# Relay_board.net
KiCad netlist of a schematic drawn in EAGLE
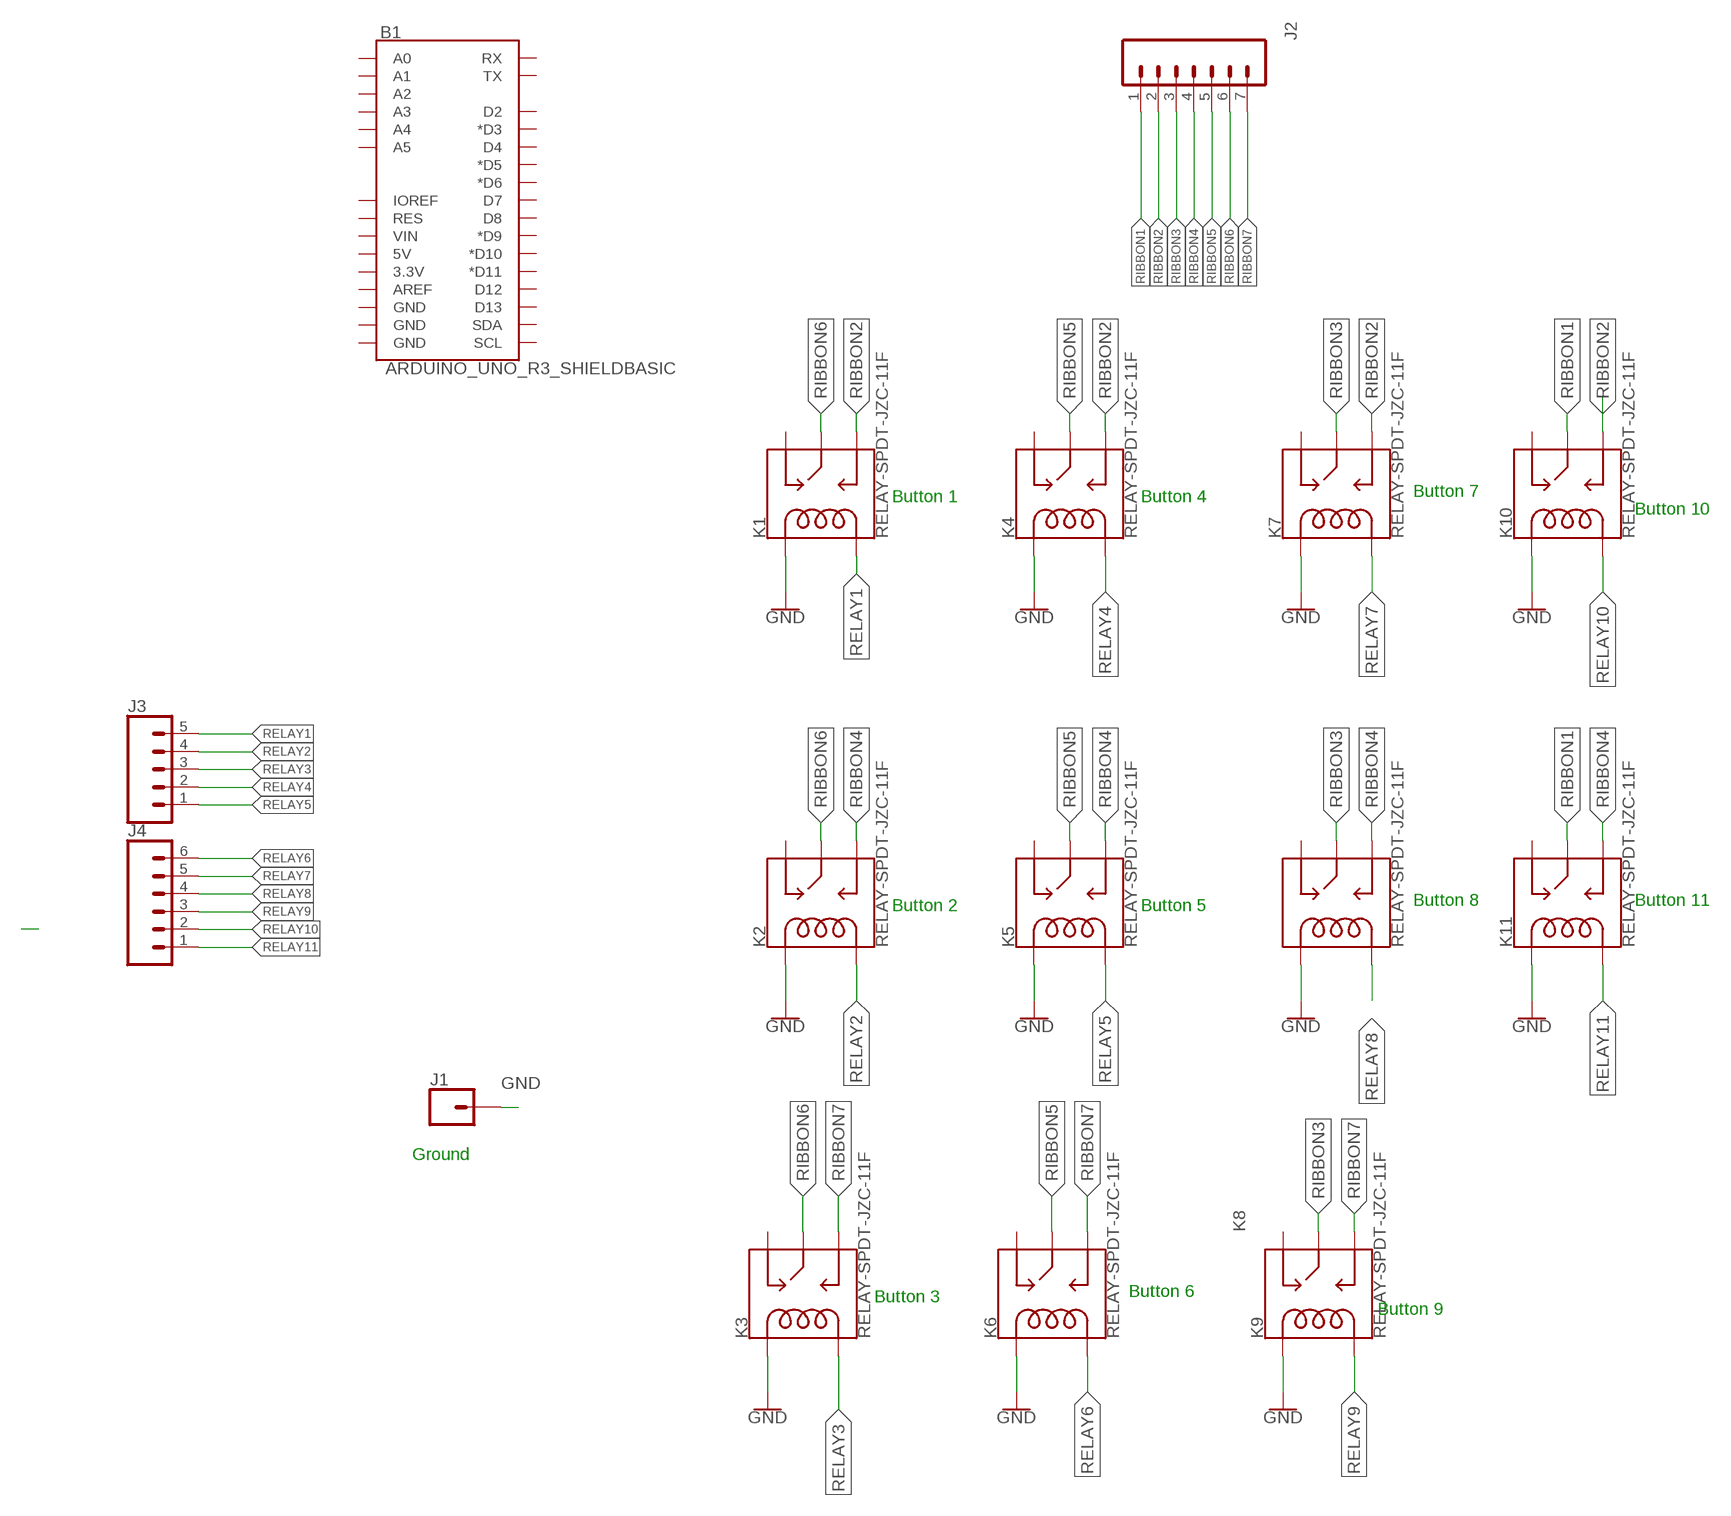
[diagram p0: schematic, sheet 1]

(export (version "E")
  (design (tool "Eeschema 10.0.6"))
  (components
    (comp (ref "B1")
      (value "ARDUINO_UNO_R3_SHIELDBASIC")
      (footprint "eagle-import:UNO_R3_SHIELD")
      (libsource (lib "eagle-import") (part "ARDUINO_UNO_R3_SHIELDBASIC"))
    )
    (comp (ref "J1")
      (value "CONN_01")
      (footprint "eagle-import:1X01")
      (libsource (lib "eagle-import") (part "CONN_01"))
    )
    (comp (ref "J2")
      (value "CONN_07")
      (footprint "eagle-import:1X07")
      (libsource (lib "eagle-import") (part "CONN_07"))
    )
    (comp (ref "J3")
      (value "CONN_05")
      (footprint "eagle-import:1X05")
      (libsource (lib "eagle-import") (part "CONN_05"))
    )
    (comp (ref "J4")
      (value "CONN_06SILK_FEMALE_PTH")
      (footprint "eagle-import:1X06")
      (libsource (lib "eagle-import") (part "CONN_06SILK_FEMALE_PTH"))
    )
    (comp (ref "K1")
      (value "RELAY-SPDT-JZC-11F")
      (footprint "eagle-import:RELAY-JZC")
      (libsource (lib "eagle-import") (part "RELAY-SPDT-JZC-11F"))
    )
    (comp (ref "K2")
      (value "RELAY-SPDT-JZC-11F")
      (footprint "eagle-import:RELAY-JZC")
      (libsource (lib "eagle-import") (part "RELAY-SPDT-JZC-11F"))
    )
    (comp (ref "K3")
      (value "RELAY-SPDT-JZC-11F")
      (footprint "eagle-import:RELAY-JZC")
      (libsource (lib "eagle-import") (part "RELAY-SPDT-JZC-11F"))
    )
    (comp (ref "K4")
      (value "RELAY-SPDT-JZC-11F")
      (footprint "eagle-import:RELAY-JZC")
      (libsource (lib "eagle-import") (part "RELAY-SPDT-JZC-11F"))
    )
    (comp (ref "K5")
      (value "RELAY-SPDT-JZC-11F")
      (footprint "eagle-import:RELAY-JZC")
      (libsource (lib "eagle-import") (part "RELAY-SPDT-JZC-11F"))
    )
    (comp (ref "K6")
      (value "RELAY-SPDT-JZC-11F")
      (footprint "eagle-import:RELAY-JZC")
      (libsource (lib "eagle-import") (part "RELAY-SPDT-JZC-11F"))
    )
    (comp (ref "K7")
      (value "RELAY-SPDT-JZC-11F")
      (footprint "eagle-import:RELAY-JZC")
      (libsource (lib "eagle-import") (part "RELAY-SPDT-JZC-11F"))
    )
    (comp (ref "K8")
      (value "RELAY-SPDT-JZC-11F")
      (footprint "eagle-import:RELAY-JZC")
      (libsource (lib "eagle-import") (part "RELAY-SPDT-JZC-11F"))
    )
    (comp (ref "K9")
      (value "RELAY-SPDT-JZC-11F")
      (footprint "eagle-import:RELAY-JZC")
      (libsource (lib "eagle-import") (part "RELAY-SPDT-JZC-11F"))
    )
    (comp (ref "K10")
      (value "RELAY-SPDT-JZC-11F")
      (footprint "eagle-import:RELAY-JZC")
      (libsource (lib "eagle-import") (part "RELAY-SPDT-JZC-11F"))
    )
    (comp (ref "K11")
      (value "RELAY-SPDT-JZC-11F")
      (footprint "eagle-import:RELAY-JZC")
      (libsource (lib "eagle-import") (part "RELAY-SPDT-JZC-11F"))
    )
  )
  (nets
    (net (code "1") (name "GND") (class "Default")
      (node (ref "J1") (pin "1") (pinfunction "1_1") (pintype "passive"))
      (node (ref "K1") (pin "5") (pinfunction "COIL1_5") (pintype "bidirectional"))
      (node (ref "K10") (pin "5") (pinfunction "COIL1_5") (pintype "bidirectional"))
      (node (ref "K11") (pin "5") (pinfunction "COIL1_5") (pintype "bidirectional"))
      (node (ref "K2") (pin "5") (pinfunction "COIL1_5") (pintype "bidirectional"))
      (node (ref "K3") (pin "5") (pinfunction "COIL1_5") (pintype "bidirectional"))
      (node (ref "K4") (pin "5") (pinfunction "COIL1_5") (pintype "bidirectional"))
      (node (ref "K5") (pin "5") (pinfunction "COIL1_5") (pintype "bidirectional"))
      (node (ref "K6") (pin "5") (pinfunction "COIL1_5") (pintype "bidirectional"))
      (node (ref "K7") (pin "5") (pinfunction "COIL1_5") (pintype "bidirectional"))
      (node (ref "K8") (pin "5") (pinfunction "COIL1_5") (pintype "bidirectional"))
      (node (ref "K9") (pin "5") (pinfunction "COIL1_5") (pintype "bidirectional"))
    )
    (net (code "2") (name "RELAY1") (class "Default")
      (node (ref "J3") (pin "5") (pinfunction "5_5") (pintype "passive"))
      (node (ref "K1") (pin "1") (pinfunction "COIL2_1") (pintype "bidirectional"))
    )
    (net (code "3") (name "RELAY2") (class "Default")
      (node (ref "J3") (pin "4") (pinfunction "4_4") (pintype "passive"))
      (node (ref "K2") (pin "1") (pinfunction "COIL2_1") (pintype "bidirectional"))
    )
    (net (code "4") (name "RELAY3") (class "Default")
      (node (ref "J3") (pin "3") (pinfunction "3_3") (pintype "passive"))
      (node (ref "K3") (pin "1") (pinfunction "COIL2_1") (pintype "bidirectional"))
    )
    (net (code "5") (name "RELAY4") (class "Default")
      (node (ref "J3") (pin "2") (pinfunction "2_2") (pintype "passive"))
      (node (ref "K4") (pin "1") (pinfunction "COIL2_1") (pintype "bidirectional"))
    )
    (net (code "6") (name "RELAY5") (class "Default")
      (node (ref "J3") (pin "1") (pinfunction "1_1") (pintype "passive"))
      (node (ref "K5") (pin "1") (pinfunction "COIL2_1") (pintype "bidirectional"))
    )
    (net (code "7") (name "RELAY6") (class "Default")
      (node (ref "J4") (pin "6") (pinfunction "6_6") (pintype "passive"))
      (node (ref "K6") (pin "1") (pinfunction "COIL2_1") (pintype "bidirectional"))
    )
    (net (code "8") (name "RELAY7") (class "Default")
      (node (ref "J4") (pin "5") (pinfunction "5_5") (pintype "passive"))
      (node (ref "K7") (pin "1") (pinfunction "COIL2_1") (pintype "bidirectional"))
    )
    (net (code "9") (name "RELAY8") (class "Default")
      (node (ref "J4") (pin "4") (pinfunction "4_4") (pintype "passive"))
      (node (ref "K8") (pin "1") (pinfunction "COIL2_1") (pintype "bidirectional"))
    )
    (net (code "10") (name "RELAY9") (class "Default")
      (node (ref "J4") (pin "3") (pinfunction "3_3") (pintype "passive"))
      (node (ref "K9") (pin "1") (pinfunction "COIL2_1") (pintype "bidirectional"))
    )
    (net (code "11") (name "RELAY10") (class "Default")
      (node (ref "J4") (pin "2") (pinfunction "2_2") (pintype "passive"))
      (node (ref "K10") (pin "1") (pinfunction "COIL2_1") (pintype "bidirectional"))
    )
    (net (code "12") (name "RELAY11") (class "Default")
      (node (ref "J4") (pin "1") (pinfunction "1_1") (pintype "passive"))
      (node (ref "K11") (pin "1") (pinfunction "COIL2_1") (pintype "bidirectional"))
    )
    (net (code "13") (name "RIBBON1") (class "Default")
      (node (ref "J2") (pin "1") (pinfunction "1_1") (pintype "passive"))
      (node (ref "K10") (pin "4") (pinfunction "MAIN_4") (pintype "bidirectional"))
      (node (ref "K11") (pin "4") (pinfunction "MAIN_4") (pintype "bidirectional"))
    )
    (net (code "14") (name "RIBBON2") (class "Default")
      (node (ref "J2") (pin "2") (pinfunction "2_2") (pintype "passive"))
      (node (ref "K1") (pin "3") (pinfunction "NO_3") (pintype "bidirectional"))
      (node (ref "K10") (pin "3") (pinfunction "NO_3") (pintype "bidirectional"))
      (node (ref "K4") (pin "3") (pinfunction "NO_3") (pintype "bidirectional"))
      (node (ref "K7") (pin "3") (pinfunction "NO_3") (pintype "bidirectional"))
    )
    (net (code "15") (name "RIBBON3") (class "Default")
      (node (ref "J2") (pin "3") (pinfunction "3_3") (pintype "passive"))
      (node (ref "K7") (pin "4") (pinfunction "MAIN_4") (pintype "bidirectional"))
      (node (ref "K8") (pin "4") (pinfunction "MAIN_4") (pintype "bidirectional"))
      (node (ref "K9") (pin "4") (pinfunction "MAIN_4") (pintype "bidirectional"))
    )
    (net (code "16") (name "RIBBON4") (class "Default")
      (node (ref "J2") (pin "4") (pinfunction "4_4") (pintype "passive"))
      (node (ref "K11") (pin "3") (pinfunction "NO_3") (pintype "bidirectional"))
      (node (ref "K2") (pin "3") (pinfunction "NO_3") (pintype "bidirectional"))
      (node (ref "K5") (pin "3") (pinfunction "NO_3") (pintype "bidirectional"))
      (node (ref "K8") (pin "3") (pinfunction "NO_3") (pintype "bidirectional"))
    )
    (net (code "17") (name "RIBBON5") (class "Default")
      (node (ref "J2") (pin "5") (pinfunction "5_5") (pintype "passive"))
      (node (ref "K4") (pin "4") (pinfunction "MAIN_4") (pintype "bidirectional"))
      (node (ref "K5") (pin "4") (pinfunction "MAIN_4") (pintype "bidirectional"))
      (node (ref "K6") (pin "4") (pinfunction "MAIN_4") (pintype "bidirectional"))
    )
    (net (code "18") (name "RIBBON6") (class "Default")
      (node (ref "J2") (pin "6") (pinfunction "6_6") (pintype "passive"))
      (node (ref "K1") (pin "4") (pinfunction "MAIN_4") (pintype "bidirectional"))
      (node (ref "K2") (pin "4") (pinfunction "MAIN_4") (pintype "bidirectional"))
      (node (ref "K3") (pin "4") (pinfunction "MAIN_4") (pintype "bidirectional"))
    )
    (net (code "19") (name "RIBBON7") (class "Default")
      (node (ref "J2") (pin "7") (pinfunction "7_7") (pintype "passive"))
      (node (ref "K3") (pin "3") (pinfunction "NO_3") (pintype "bidirectional"))
      (node (ref "K6") (pin "3") (pinfunction "NO_3") (pintype "bidirectional"))
      (node (ref "K9") (pin "3") (pinfunction "NO_3") (pintype "bidirectional"))
    )
    (net (code "20") (name "unconnected-(B1-*D3-PadD3)") (class "Default")
      (node (ref "B1") (pin "D3") (pinfunction "*D3_D3") (pintype "bidirectional"))
    )
    (net (code "21") (name "unconnected-(B1-*D5-PadD5)") (class "Default")
      (node (ref "B1") (pin "D5") (pinfunction "*D5_D5") (pintype "bidirectional"))
    )
    (net (code "22") (name "unconnected-(B1-*D6-PadD6)") (class "Default")
      (node (ref "B1") (pin "D6") (pinfunction "*D6_D6") (pintype "bidirectional"))
    )
    (net (code "23") (name "unconnected-(B1-*D9-PadD9)") (class "Default")
      (node (ref "B1") (pin "D9") (pinfunction "*D9_D9") (pintype "bidirectional"))
    )
    (net (code "24") (name "unconnected-(B1-*D10-PadD10)") (class "Default")
      (node (ref "B1") (pin "D10") (pinfunction "*D10_D10") (pintype "bidirectional"))
    )
    (net (code "25") (name "unconnected-(B1-*D11-PadD11)") (class "Default")
      (node (ref "B1") (pin "D11") (pinfunction "*D11_D11") (pintype "bidirectional"))
    )
    (net (code "26") (name "unconnected-(B1-GND-PadGND@0)") (class "Default")
      (node (ref "B1") (pin "GND@0") (pinfunction "GND_GND@0") (pintype "bidirectional"))
    )
    (net (code "27") (name "unconnected-(B1-GND-PadGND@1)") (class "Default")
      (node (ref "B1") (pin "GND@1") (pinfunction "GND_GND@1") (pintype "bidirectional"))
    )
    (net (code "28") (name "unconnected-(B1-GND-PadGND@2)") (class "Default")
      (node (ref "B1") (pin "GND@2") (pinfunction "GND_GND@2") (pintype "bidirectional"))
    )
    (net (code "29") (name "unconnected-(B1-Pad3.3V)") (class "Default")
      (node (ref "B1") (pin "3.3V") (pinfunction "3.3V_3.3V") (pintype "bidirectional"))
    )
    (net (code "30") (name "unconnected-(B1-Pad5V)") (class "Default")
      (node (ref "B1") (pin "5V") (pinfunction "5V_5V") (pintype "bidirectional"))
    )
    (net (code "31") (name "unconnected-(B1-PadA0)") (class "Default")
      (node (ref "B1") (pin "A0") (pinfunction "A0_A0") (pintype "bidirectional"))
    )
    (net (code "32") (name "unconnected-(B1-PadA1)") (class "Default")
      (node (ref "B1") (pin "A1") (pinfunction "A1_A1") (pintype "bidirectional"))
    )
    (net (code "33") (name "unconnected-(B1-PadA2)") (class "Default")
      (node (ref "B1") (pin "A2") (pinfunction "A2_A2") (pintype "bidirectional"))
    )
    (net (code "34") (name "unconnected-(B1-PadA3)") (class "Default")
      (node (ref "B1") (pin "A3") (pinfunction "A3_A3") (pintype "bidirectional"))
    )
    (net (code "35") (name "unconnected-(B1-PadA4)") (class "Default")
      (node (ref "B1") (pin "A4") (pinfunction "A4_A4") (pintype "bidirectional"))
    )
    (net (code "36") (name "unconnected-(B1-PadA5)") (class "Default")
      (node (ref "B1") (pin "A5") (pinfunction "A5_A5") (pintype "bidirectional"))
    )
    (net (code "37") (name "unconnected-(B1-PadAREF)") (class "Default")
      (node (ref "B1") (pin "AREF") (pinfunction "AREF_AREF") (pintype "bidirectional"))
    )
    (net (code "38") (name "unconnected-(B1-PadD2)") (class "Default")
      (node (ref "B1") (pin "D2") (pinfunction "D2_D2") (pintype "bidirectional"))
    )
    (net (code "39") (name "unconnected-(B1-PadD4)") (class "Default")
      (node (ref "B1") (pin "D4") (pinfunction "D4_D4") (pintype "bidirectional"))
    )
    (net (code "40") (name "unconnected-(B1-PadD7)") (class "Default")
      (node (ref "B1") (pin "D7") (pinfunction "D7_D7") (pintype "bidirectional"))
    )
    (net (code "41") (name "unconnected-(B1-PadD8)") (class "Default")
      (node (ref "B1") (pin "D8") (pinfunction "D8_D8") (pintype "bidirectional"))
    )
    (net (code "42") (name "unconnected-(B1-PadD12)") (class "Default")
      (node (ref "B1") (pin "D12") (pinfunction "D12_D12") (pintype "bidirectional"))
    )
    (net (code "43") (name "unconnected-(B1-PadD13)") (class "Default")
      (node (ref "B1") (pin "D13") (pinfunction "D13_D13") (pintype "bidirectional"))
    )
    (net (code "44") (name "unconnected-(B1-PadIOREF)") (class "Default")
      (node (ref "B1") (pin "IOREF") (pinfunction "IOREF_IOREF") (pintype "bidirectional"))
    )
    (net (code "45") (name "unconnected-(B1-PadRES)") (class "Default")
      (node (ref "B1") (pin "RES") (pinfunction "RES_RES") (pintype "bidirectional"))
    )
    (net (code "46") (name "unconnected-(B1-PadRX)") (class "Default")
      (node (ref "B1") (pin "RX") (pinfunction "RX_RX") (pintype "bidirectional"))
    )
    (net (code "47") (name "unconnected-(B1-PadSCL)") (class "Default")
      (node (ref "B1") (pin "SCL") (pinfunction "SCL_SCL") (pintype "bidirectional"))
    )
    (net (code "48") (name "unconnected-(B1-PadSDA)") (class "Default")
      (node (ref "B1") (pin "SDA") (pinfunction "SDA_SDA") (pintype "bidirectional"))
    )
    (net (code "49") (name "unconnected-(B1-PadTX)") (class "Default")
      (node (ref "B1") (pin "TX") (pinfunction "TX_TX") (pintype "bidirectional"))
    )
    (net (code "50") (name "unconnected-(B1-PadVIN)") (class "Default")
      (node (ref "B1") (pin "VIN") (pinfunction "VIN_VIN") (pintype "bidirectional"))
    )
    (net (code "51") (name "unconnected-(K1-NC-Pad2)") (class "Default")
      (node (ref "K1") (pin "2") (pinfunction "NC_2") (pintype "bidirectional"))
    )
    (net (code "52") (name "unconnected-(K2-NC-Pad2)") (class "Default")
      (node (ref "K2") (pin "2") (pinfunction "NC_2") (pintype "bidirectional"))
    )
    (net (code "53") (name "unconnected-(K3-NC-Pad2)") (class "Default")
      (node (ref "K3") (pin "2") (pinfunction "NC_2") (pintype "bidirectional"))
    )
    (net (code "54") (name "unconnected-(K4-NC-Pad2)") (class "Default")
      (node (ref "K4") (pin "2") (pinfunction "NC_2") (pintype "bidirectional"))
    )
    (net (code "55") (name "unconnected-(K5-NC-Pad2)") (class "Default")
      (node (ref "K5") (pin "2") (pinfunction "NC_2") (pintype "bidirectional"))
    )
    (net (code "56") (name "unconnected-(K6-NC-Pad2)") (class "Default")
      (node (ref "K6") (pin "2") (pinfunction "NC_2") (pintype "bidirectional"))
    )
    (net (code "57") (name "unconnected-(K7-NC-Pad2)") (class "Default")
      (node (ref "K7") (pin "2") (pinfunction "NC_2") (pintype "bidirectional"))
    )
    (net (code "58") (name "unconnected-(K8-NC-Pad2)") (class "Default")
      (node (ref "K8") (pin "2") (pinfunction "NC_2") (pintype "bidirectional"))
    )
    (net (code "59") (name "unconnected-(K9-NC-Pad2)") (class "Default")
      (node (ref "K9") (pin "2") (pinfunction "NC_2") (pintype "bidirectional"))
    )
    (net (code "60") (name "unconnected-(K10-NC-Pad2)") (class "Default")
      (node (ref "K10") (pin "2") (pinfunction "NC_2") (pintype "bidirectional"))
    )
    (net (code "61") (name "unconnected-(K11-NC-Pad2)") (class "Default")
      (node (ref "K11") (pin "2") (pinfunction "NC_2") (pintype "bidirectional"))
    )
  )
)
